# MotionDetector.net
KiCad netlist of a schematic drawn in EAGLE
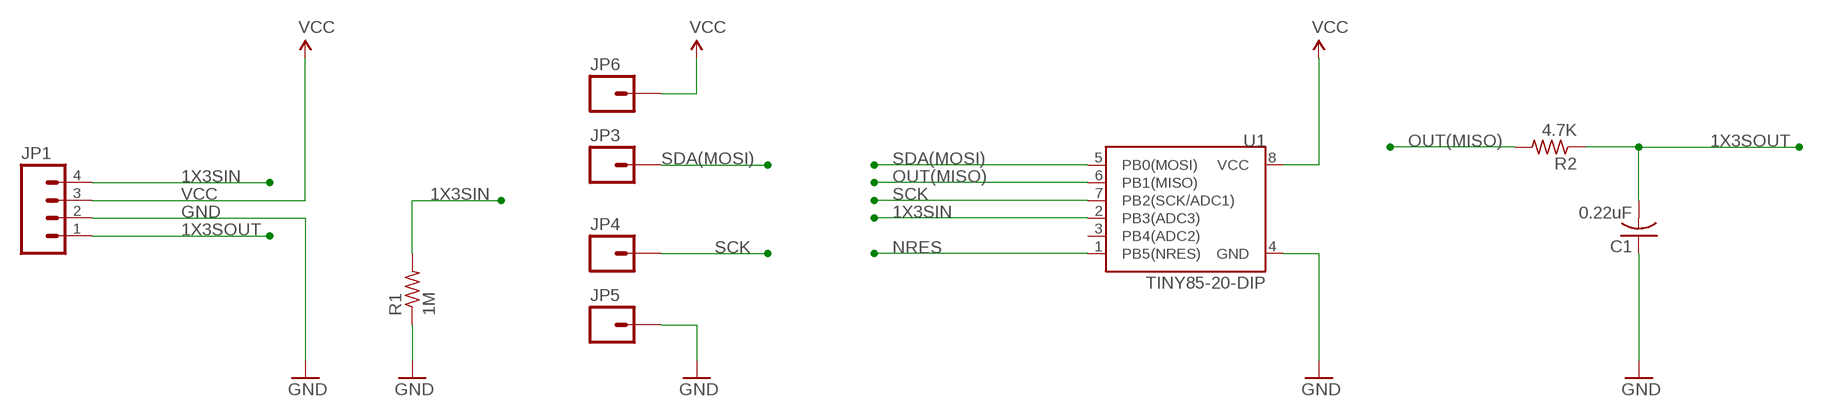
[diagram p0: schematic, sheet 1]

(export (version "E")
  (design (tool "Eeschema 10.0.6"))
  (components
    (comp (ref "C1")
      (value "0.22uF")
      (footprint "eagle-import:C0402")
      (libsource (lib "eagle-import") (part "C-USC0402"))
    )
    (comp (ref "JP1")
      (value "M04PTH")
      (footprint "eagle-import:1X04")
      (libsource (lib "eagle-import") (part "M04PTH"))
    )
    (comp (ref "JP3")
      (value "M01PTH")
      (footprint "eagle-import:1X01")
      (libsource (lib "eagle-import") (part "M01PTH"))
    )
    (comp (ref "JP4")
      (value "M01PTH")
      (footprint "eagle-import:1X01")
      (libsource (lib "eagle-import") (part "M01PTH"))
    )
    (comp (ref "JP5")
      (value "M01PTH")
      (footprint "eagle-import:1X01")
      (libsource (lib "eagle-import") (part "M01PTH"))
    )
    (comp (ref "JP6")
      (value "M01PTH")
      (footprint "eagle-import:1X01")
      (libsource (lib "eagle-import") (part "M01PTH"))
    )
    (comp (ref "R1")
      (value "1M")
      (footprint "eagle-import:R0603")
      (libsource (lib "eagle-import") (part "R-US_R0603"))
    )
    (comp (ref "R2")
      (value "4.7K")
      (footprint "eagle-import:R0603")
      (libsource (lib "eagle-import") (part "R-US_R0603"))
    )
    (comp (ref "U1")
      (value "TINY85-20-DIP")
      (footprint "eagle-import:DIP08")
      (libsource (lib "eagle-import") (part "ATTINY45TINY85-20-DIP"))
    )
  )
  (nets
    (net (code "1") (name "/1X3SIN") (class "Default")
      (node (ref "JP1") (pin "4") (pinfunction "4_4") (pintype "passive"))
      (node (ref "R1") (pin "2") (pinfunction "2_2") (pintype "passive"))
      (node (ref "U1") (pin "2") (pinfunction "PB3(ADC3)_2") (pintype "bidirectional"))
    )
    (net (code "2") (name "/1X3SOUT") (class "Default")
      (node (ref "C1") (pin "2") (pinfunction "2_2") (pintype "passive"))
      (node (ref "JP1") (pin "1") (pinfunction "1_1") (pintype "passive"))
      (node (ref "R2") (pin "1") (pinfunction "1_1") (pintype "passive"))
    )
    (net (code "3") (name "/NRES") (class "Default")
      (node (ref "U1") (pin "1") (pinfunction "PB5(NRES)_1") (pintype "bidirectional"))
    )
    (net (code "4") (name "/OUT(MISO)") (class "Default")
      (node (ref "R2") (pin "2") (pinfunction "2_2") (pintype "passive"))
      (node (ref "U1") (pin "6") (pinfunction "PB1(MISO)_6") (pintype "bidirectional"))
    )
    (net (code "5") (name "/SCK") (class "Default")
      (node (ref "JP4") (pin "1") (pinfunction "1_1") (pintype "passive"))
      (node (ref "U1") (pin "7") (pinfunction "PB2(SCK/ADC1)_7") (pintype "bidirectional"))
    )
    (net (code "6") (name "/SDA(MOSI)") (class "Default")
      (node (ref "JP3") (pin "1") (pinfunction "1_1") (pintype "passive"))
      (node (ref "U1") (pin "5") (pinfunction "PB0(MOSI)_5") (pintype "bidirectional"))
    )
    (net (code "7") (name "GND") (class "Default")
      (node (ref "C1") (pin "1") (pinfunction "1_1") (pintype "passive"))
      (node (ref "JP1") (pin "2") (pinfunction "2_2") (pintype "passive"))
      (node (ref "JP5") (pin "1") (pinfunction "1_1") (pintype "passive"))
      (node (ref "R1") (pin "1") (pinfunction "1_1") (pintype "passive"))
      (node (ref "U1") (pin "4") (pinfunction "GND_4") (pintype "bidirectional"))
    )
    (net (code "8") (name "VCC") (class "Default")
      (node (ref "JP1") (pin "3") (pinfunction "3_3") (pintype "passive"))
      (node (ref "JP6") (pin "1") (pinfunction "1_1") (pintype "passive"))
      (node (ref "U1") (pin "8") (pinfunction "VCC_8") (pintype "bidirectional"))
    )
    (net (code "9") (name "unconnected-(U1-PB4(ADC2)-Pad3)") (class "Default")
      (node (ref "U1") (pin "3") (pinfunction "PB4(ADC2)_3") (pintype "bidirectional"))
    )
  )
)
